# RNG01.net
KiCad netlist of a schematic drawn in EAGLE
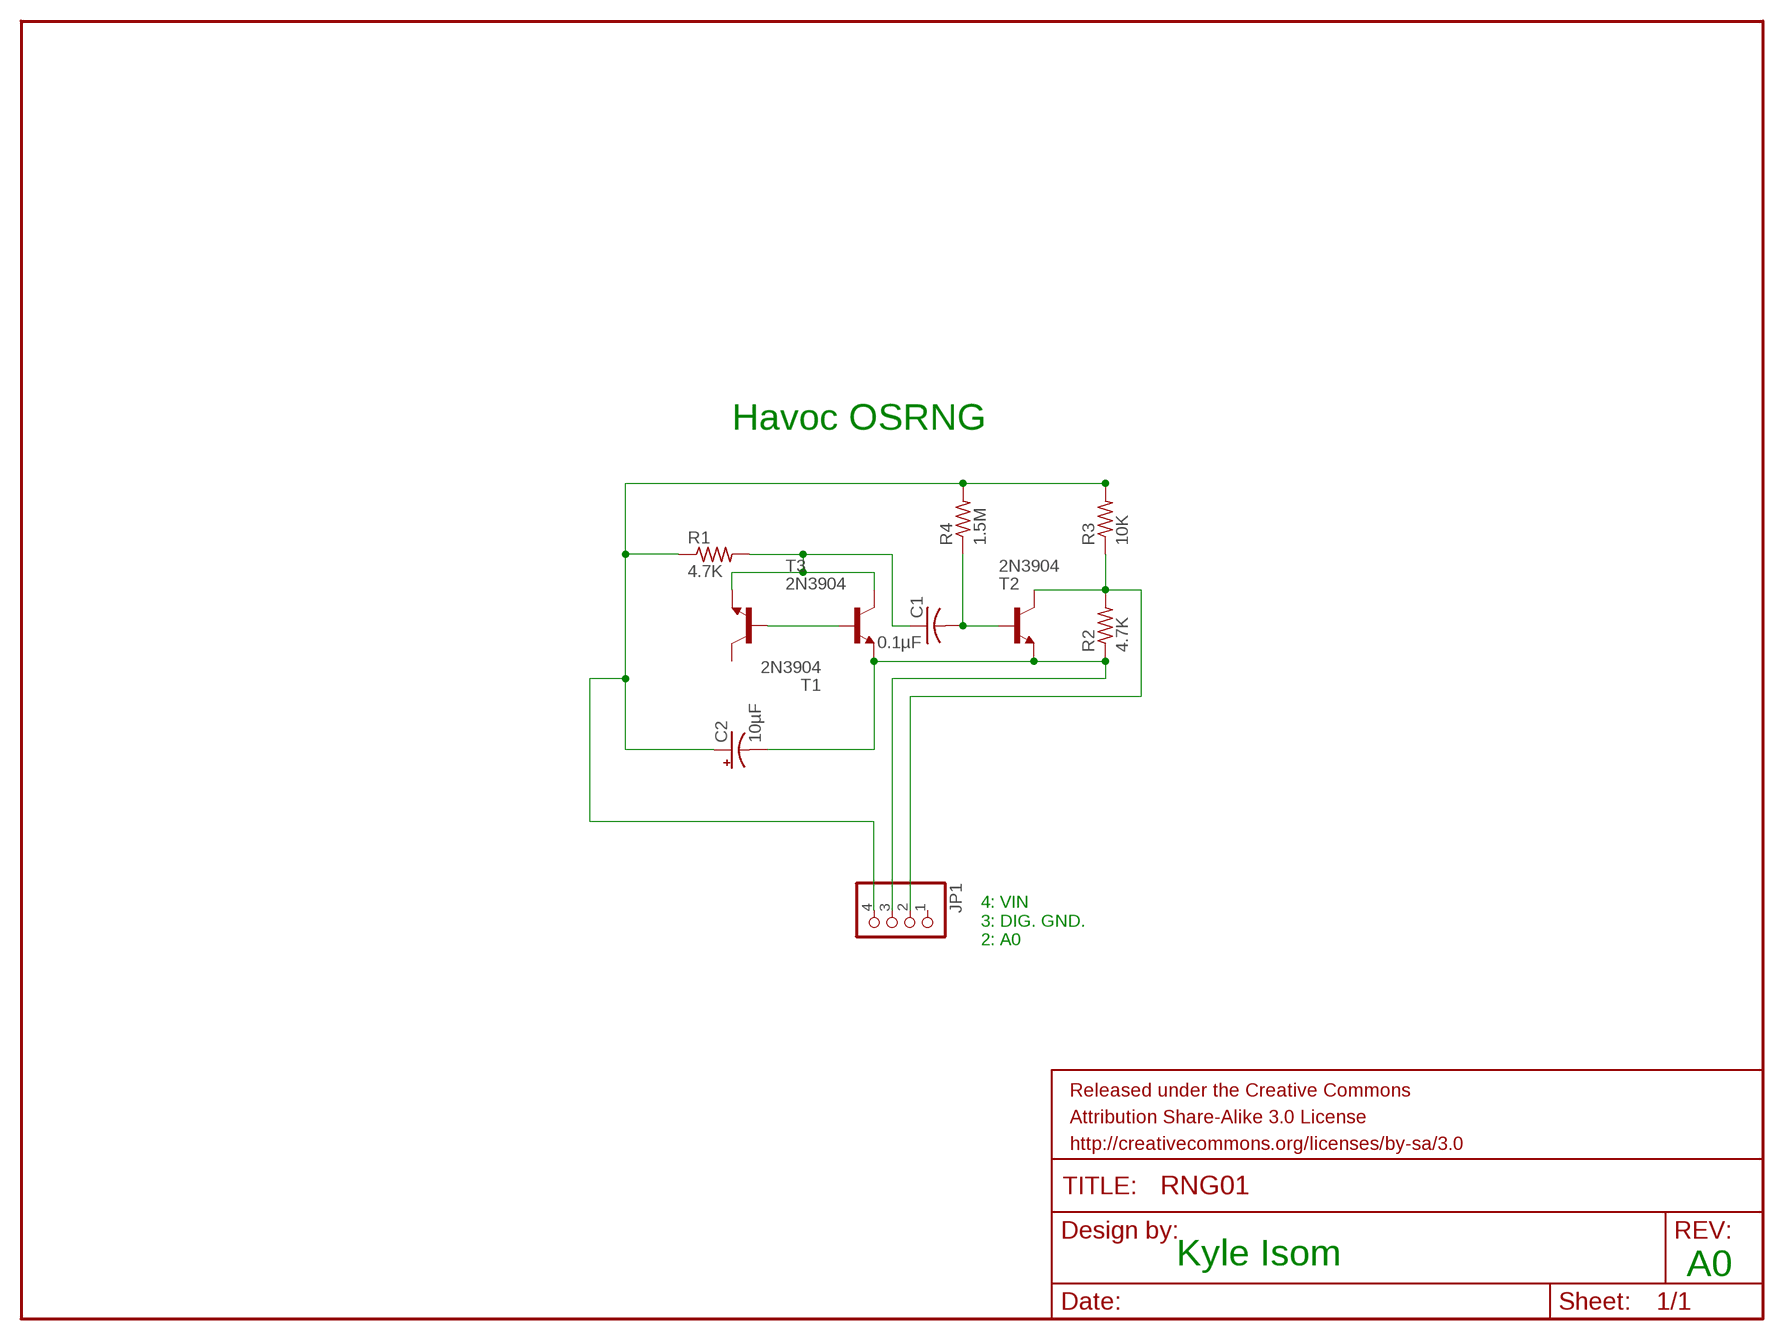
[diagram p0: schematic, sheet 1]

(export (version "E")
  (design (tool "Eeschema 10.0.6"))
  (components
    (comp (ref "C1")
      (value "0.1µF")
      (footprint "eagle-import:C050-030X075")
      (libsource (lib "eagle-import") (part "C-US050-030X075"))
    )
    (comp (ref "C2")
      (value "10µF")
      (footprint "eagle-import:E2-5")
      (libsource (lib "eagle-import") (part "CPOL-USE2-5"))
    )
    (comp (ref "FRAME1")
      (value "FRAME-LETTER")
      (footprint "eagle-import:CREATIVE_COMMONS")
      (libsource (lib "eagle-import") (part "FRAME-LETTER"))
    )
    (comp (ref "JP1")
      (value "PINHD-1X4")
      (footprint "eagle-import:1X04")
      (libsource (lib "eagle-import") (part "PINHD-1X4"))
    )
    (comp (ref "R1")
      (value "4.7K")
      (footprint "eagle-import:0207_7")
      (libsource (lib "eagle-import") (part "R-US_0207/7"))
    )
    (comp (ref "R2")
      (value "4.7K")
      (footprint "eagle-import:0207_7")
      (libsource (lib "eagle-import") (part "R-US_0207/7"))
    )
    (comp (ref "R3")
      (value "10K")
      (footprint "eagle-import:0207_7")
      (libsource (lib "eagle-import") (part "R-US_0207/7"))
    )
    (comp (ref "R4")
      (value "1.5M")
      (footprint "eagle-import:0207_7")
      (libsource (lib "eagle-import") (part "R-US_0207/7"))
    )
    (comp (ref "T1")
      (value "2N3904")
      (footprint "eagle-import:TO92")
      (libsource (lib "eagle-import") (part "2N3904"))
    )
    (comp (ref "T2")
      (value "2N3904")
      (footprint "eagle-import:TO92")
      (libsource (lib "eagle-import") (part "2N3904"))
    )
    (comp (ref "T3")
      (value "2N3904")
      (footprint "eagle-import:TO92")
      (libsource (lib "eagle-import") (part "2N3904"))
    )
  )
  (nets
    (net (code "1") (name "Net-(C2-Pad+)") (class "Default")
      (node (ref "C2") (pin "+") (pinfunction "+_+") (pintype "passive"))
      (node (ref "JP1") (pin "4") (pinfunction "4_4") (pintype "passive"))
      (node (ref "R1") (pin "1") (pinfunction "1_1") (pintype "passive"))
      (node (ref "R3") (pin "2") (pinfunction "2_2") (pintype "passive"))
      (node (ref "R4") (pin "2") (pinfunction "2_2") (pintype "passive"))
    )
    (net (code "2") (name "Net-(T1-B)") (class "Default")
      (node (ref "T1") (pin "2") (pinfunction "B_2") (pintype "passive"))
      (node (ref "T3") (pin "2") (pinfunction "B_2") (pintype "passive"))
    )
    (net (code "3") (name "Net-(T1-E)") (class "Default")
      (node (ref "C1") (pin "1") (pinfunction "1_1") (pintype "passive"))
      (node (ref "R1") (pin "2") (pinfunction "2_2") (pintype "passive"))
      (node (ref "T1") (pin "3") (pinfunction "E_3") (pintype "passive"))
      (node (ref "T3") (pin "1") (pinfunction "C_1") (pintype "passive"))
    )
    (net (code "4") (name "Net-(T2-B)") (class "Default")
      (node (ref "C1") (pin "2") (pinfunction "2_2") (pintype "passive"))
      (node (ref "R4") (pin "1") (pinfunction "1_1") (pintype "passive"))
      (node (ref "T2") (pin "2") (pinfunction "B_2") (pintype "passive"))
    )
    (net (code "5") (name "Net-(T2-C)") (class "Default")
      (node (ref "JP1") (pin "2") (pinfunction "2_2") (pintype "passive"))
      (node (ref "R2") (pin "2") (pinfunction "2_2") (pintype "passive"))
      (node (ref "R3") (pin "1") (pinfunction "1_1") (pintype "passive"))
      (node (ref "T2") (pin "1") (pinfunction "C_1") (pintype "passive"))
    )
    (net (code "6") (name "Net-(T2-E)") (class "Default")
      (node (ref "C2") (pin "-") (pinfunction "-_-") (pintype "passive"))
      (node (ref "JP1") (pin "3") (pinfunction "3_3") (pintype "passive"))
      (node (ref "R2") (pin "1") (pinfunction "1_1") (pintype "passive"))
      (node (ref "T2") (pin "3") (pinfunction "E_3") (pintype "passive"))
      (node (ref "T3") (pin "3") (pinfunction "E_3") (pintype "passive"))
    )
    (net (code "7") (name "unconnected-(JP1-Pad1)") (class "Default")
      (node (ref "JP1") (pin "1") (pinfunction "1_1") (pintype "passive"))
    )
    (net (code "8") (name "unconnected-(T1-C-Pad1)") (class "Default")
      (node (ref "T1") (pin "1") (pinfunction "C_1") (pintype "passive"))
    )
  )
)
